# PowerMeter_PowerSupply.net
KiCad netlist of a schematic drawn in Altium Designer
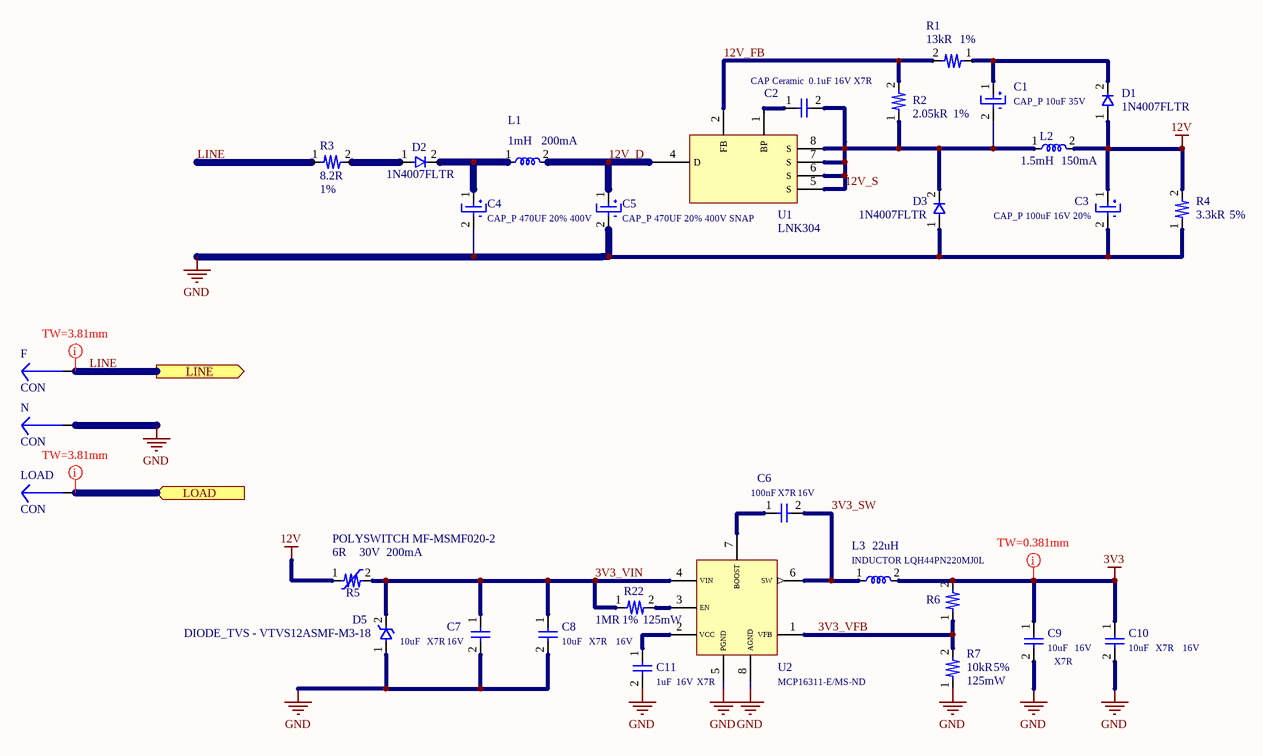
[diagram p0: PowerMeter_PowerSupply.SchDoc]

(export (version "E")
  (design (tool "Eeschema 10.0.6"))
  (components
    (comp (ref "C1")
      (value "CAP_P 10uF 35V")
      (footprint "CAP100RP")
      (description "Cap Aluminum 10uF 35V 20% Radial 2000 hr 85°C Ammo Pack")
      (fields
        (field (name "MANUFACTURER") "Panasonic")
        (field (name "MANUFACTURER PART NUMBER") "ECA-1VM100B")
      )
      (libsource (lib "PowerMeter") (part "CAP_P"))
    )
    (comp (ref "C2")
      (value "CAP Ceramic  0.1uF 16V X7R")
      (footprint "C_0805")
      (description "Cap Ceramic 0.1uF 16V X7R 10% SMD 0805 125C Paper T/R")
      (fields
        (field (name "MANUFACTURER") "Yageo")
        (field (name "MANUFACTURER PART NUMBER") "CC0805KPX7R7BB104")
      )
      (libsource (lib "PowerMeter") (part "CAP_NP"))
    )
    (comp (ref "C3")
      (value "CAP_P 100uF 16V 20%")
      (footprint "CAP100RP")
      (description "Cap Aluminum 100uF 16V 20% (5 X 11mm) Radial 2.5mm 180mA 2000h 85°C Ammo Pack")
      (fields
        (field (name "MANUFACTURER") "Panasonic")
        (field (name "MANUFACTURER PART NUMBER") "ECA-1CM101I")
      )
      (libsource (lib "PowerMeter") (part "CAP_P"))
    )
    (comp (ref "C4")
      (value "CAP_P 470UF 20% 400V")
      (footprint "CAP400RP")
      (description "CAP ALUM 470UF 20% 400V SNAP")
      (fields
        (field (name "MANUFACTURER") "Rubycon")
        (field (name "MANUFACTURER PART NUMBER") "400USG470MEFC25X50")
      )
      (libsource (lib "PowerMeter") (part "CAP_P"))
    )
    (comp (ref "C5")
      (value "CAP_P 470UF 20% 400V SNAP")
      (footprint "CAP400RP")
      (description "CAP ALUM 470UF 20% 400V")
      (fields
        (field (name "MANUFACTURER") "Rubycon")
        (field (name "MANUFACTURER PART NUMBER") "400USG470MEFC25X50")
      )
      (libsource (lib "PowerMeter") (part "CAP_P"))
    )
    (comp (ref "C6")
      (value "CAP Ceramic  0.1uF 16V X7R")
      (footprint "C_0805")
      (description "Cap Ceramic 0.1uF 16V X7R 10% SMD 0805 125C Paper T/R")
      (fields
        (field (name "MANUFACTURER") "Yageo")
        (field (name "MANUFACTURER PART NUMBER") "CC0805KPX7R7BB104")
        (field (name "CAPACITANCE") "100nF")
        (field (name "VOLTAGE RATING (DC)") "16V")
        (field (name "DIELECTRIC") "X7R")
      )
      (libsource (lib "PowerMeter") (part "CAP_NP"))
    )
    (comp (ref "C7")
      (value "CAP Ceramic  10uF 16V X7R")
      (footprint "C_1206")
      (description "CL31 Series 1206 10 uF 16 V ±10% Tolerance X7R Multilayer Ceramic Capacitor")
      (fields
        (field (name "MANUFACTURER") "Samsung")
        (field (name "MANUFACTURER PART NUMBER") "CL31B106KOHNNNF")
        (field (name "CAPACITANCE") "10uF")
        (field (name "DIELECTRIC") "X7R")
        (field (name "VOLTAGE RATING") "16V")
      )
      (libsource (lib "PowerMeter") (part "CAP_NP"))
    )
    (comp (ref "C8")
      (value "CAP Ceramic  10uF 16V X7R")
      (footprint "C_1206")
      (description "CL31 Series 1206 10 uF 16 V ±10% Tolerance X7R Multilayer Ceramic Capacitor")
      (fields
        (field (name "MANUFACTURER") "Samsung")
        (field (name "MANUFACTURER PART NUMBER") "CL31B106KOHNNNF")
        (field (name "CAPACITANCE") "10uF")
        (field (name "DIELECTRIC") "X7R")
        (field (name "VOLTAGE RATING") "16V")
      )
      (libsource (lib "PowerMeter") (part "CAP_NP"))
    )
    (comp (ref "C9")
      (value "CAP Ceramic 10uF 16V X7R")
      (footprint "C_1206")
      (description "CL31 Series 1206 10 uF 16 V ±10% Tolerance X7R Multilayer Ceramic Capacitor")
      (fields
        (field (name "MANUFACTURER") "Samsung")
        (field (name "MANUFACTURER PART NUMBER") "CL31B106KOHNNNF")
        (field (name "CAPACITANCE") "10uF")
        (field (name "DIELECTRIC") "X7R")
        (field (name "VOLTAGE RATING") "16V")
      )
      (libsource (lib "PowerMeter") (part "CAP_NP"))
    )
    (comp (ref "C10")
      (value "CAP Ceramic 10uF 16V X7R")
      (footprint "C_1206")
      (description "CL31 Series 1206 10 uF 16 V ±10% Tolerance X7R Multilayer Ceramic Capacitor")
      (fields
        (field (name "MANUFACTURER") "Samsung")
        (field (name "MANUFACTURER PART NUMBER") "CL31B106KOHNNNF")
        (field (name "CAPACITANCE") "10uF")
        (field (name "DIELECTRIC") "X7R")
        (field (name "VOLTAGE RATING") "16V")
      )
      (libsource (lib "PowerMeter") (part "CAP_NP"))
    )
    (comp (ref "C11")
      (value "CAP Ceramic  1uF 16V X7R")
      (footprint "C_0805")
      (description "Cap Ceramic 1uF 16V X7R 10% Pad SMD 0805 125C T/R")
      (fields
        (field (name "MANUFACTURER") "Samsung")
        (field (name "MANUFACTURER PART NUMBER") "CL21B105KOFNNNF")
        (field (name "CAPACITANCE") "1uF")
        (field (name "DIELECTRIC") "X7R")
        (field (name "VOLTAGE RATING") "16V")
      )
      (libsource (lib "PowerMeter") (part "CAP_NP"))
    )
    (comp (ref "D1")
      (value "DIODE")
      (footprint "SOD_123")
      (description "Standard Rectifier 1000V SOD-123")
      (fields
        (field (name "MANUFACTURER") "Sangdest Microelectronics")
        (field (name "MANUFACTURER PART NUMBER") "1N4007FLTR")
      )
      (libsource (lib "PowerMeter") (part "DIODE"))
    )
    (comp (ref "D2")
      (value "Standard Rectifier 1000V SOD-123")
      (footprint "SOD_123")
      (fields
        (field (name "MANUFACTURER") "Sangdest Microelectronics")
        (field (name "MANUFACTURER PART NUMBER") "1N4007FLTR")
      )
      (libsource (lib "PowerMeter") (part "DIODE"))
    )
    (comp (ref "D3")
      (value "DIODE 1N4007FLTR")
      (footprint "SOD_123")
      (description "Standard Rectifier 1000V SOD-123")
      (fields
        (field (name "MANUFACTURER") "Sangdest Microelectronics")
        (field (name "MANUFACTURER PART NUMBER") "1N4007FLTR")
      )
      (libsource (lib "PowerMeter") (part "DIODE"))
    )
    (comp (ref "D5")
      (value "DIODE_TVS - VTVS12ASMF-M3-18")
      (footprint "SOD_923")
      (description "Esd Protection Diode Smf Do219Ab5%; 12.4V; ir0.05 A; ip19.5A; p400W; cd807Pf")
      (fields
        (field (name "MANUFACTURER") "Vishay")
        (field (name "MANUFACTURER PART NUMBER") "VTVS12ASMF-M3-18")
      )
      (libsource (lib "PowerMeter") (part "DIODE_TVS"))
    )
    (comp (ref "F")
      (value "CON")
      (footprint "HOLE 2.8")
      (description "Hole")
      (libsource (lib "PowerMeter") (part "CON"))
    )
    (comp (ref "L1")
      (value "INDUCTOR RLH0912-102KL")
      (footprint "LQH44")
      (description "Magnetics - Fixed Inductor Through Hole / Bulk, Bag Packaging Rohs Compliant: Yes")
      (fields
        (field (name "MANUFACTURER") "Bourns")
        (field (name "MANUFACTURER PART NUMBER") "RLH0912-102KL")
        (field (name "CURRENT RATING") "200mA")
        (field (name "INDUCTANCE") "1mH")
      )
      (libsource (lib "PowerMeter") (part "INDUCTOR"))
    )
    (comp (ref "L2")
      (value "INDUCTOR AIUR-16-152K")
      (footprint "LQH44")
      (description "Inductor Power Unshielded Drum Core 1500uH 10% 10KHz Ferrite 0.15A 3.5Ohm DCR RDL Box")
      (fields
        (field (name "MANUFACTURER") "Abracon")
        (field (name "MANUFACTURER PART NUMBER") "AIUR-16-152K")
        (field (name "INDUCTANCE") "1.5mH")
        (field (name "CURRENT RATING") "150mA")
      )
      (libsource (lib "PowerMeter") (part "INDUCTOR"))
    )
    (comp (ref "L3")
      (value "INDUCTOR LQH44PN220MJ0L")
      (footprint "LQH44")
      (description "Inductor Power Chip Shielded Wirewound 22uH 20% 100KHz Ferrite 0.55A 0.576Ohm DCR 1515 T/R")
      (fields
        (field (name "MANUFACTURER") "Murata")
        (field (name "MANUFACTURER PART NUMBER") "LQH44PN220MJ0L")
        (field (name "INDUCTANCE") "22uH")
      )
      (libsource (lib "PowerMeter") (part "INDUCTOR"))
    )
    (comp (ref "LOAD")
      (value "CON")
      (footprint "HOLE 2.8")
      (description "Hole")
      (libsource (lib "PowerMeter") (part "CON"))
    )
    (comp (ref "N")
      (value "CON")
      (footprint "HOLE 2.8")
      (description "Hole")
      (libsource (lib "PowerMeter") (part "CON"))
    )
    (comp (ref "R1")
      (value "RES 13K Ohm 1% 1/8W")
      (footprint "R_0805")
      (description "Res Thick Film 0805 13K Ohm 1% 1/8W ±100ppm/°C Molded SMD SMD Paper T/R")
      (fields
        (field (name "MANUFACTURER") "Stackpole Electronics")
        (field (name "MANUFACTURER PART NUMBER") "RMCF0805FG13K0")
        (field (name "RESISTANCE") "13kR")
        (field (name "TOLERANCE") "1%")
      )
      (libsource (lib "PowerMeter") (part "RES"))
    )
    (comp (ref "R2")
      (value "RES 2.05K Ohm 1% 1/8W")
      (footprint "R_0805")
      (description "Res Thick Film 0805 2.05K Ohm 1% 1/8W ±200ppm/°C Molded SMD SMD Paper T/R")
      (fields
        (field (name "MANUFACTURER") "Stackpole Electronics")
        (field (name "MANUFACTURER PART NUMBER") "RMCF0805FG2K05")
        (field (name "RESISTANCE") "2.05kR")
        (field (name "TOLERANCE") "1%")
      )
      (libsource (lib "PowerMeter") (part "RES"))
    )
    (comp (ref "R3")
      (value "RES 0805 8.2 Ohm 1W")
      (footprint "R_0805")
      (description "Res Thin Film 0805 8.2 Ohm 1% 1W ±100ppm/C Pad SMD T/R")
      (fields
        (field (name "MANUFACTURER") "Vishay Dale Thin Film")
        (field (name "MANUFACTURER PART NUMBER") "PCAN0805K8R20FST5")
        (field (name "RESISTANCE") "8.2R")
        (field (name "TOLERANCE") "1%")
      )
      (libsource (lib "PowerMeter") (part "RES"))
    )
    (comp (ref "R4")
      (value "RES  3.3 K Ohms 0.125W; +/-5%")
      (footprint "R_0805")
      (description "Resistor, Thick Film Chip; 3.3 K Ohms; Case 0805; 0.125W; +/-5%; SMD; 200ppm/K; 150V")
      (fields
        (field (name "MANUFACTURER") "Vishay Dale")
        (field (name "MANUFACTURER PART NUMBER") "CRCW08053K30JNTA")
        (field (name "TOLERANCE") "5%")
        (field (name "RESISTANCE") "3.3kR")
      )
      (libsource (lib "PowerMeter") (part "RES"))
    )
    (comp (ref "R5")
      (value "POLYSWITCH MF-MSMF020-2")
      (footprint "NANOSMDC")
      (fields
        (field (name "MANUFACTURER") "Bourns")
        (field (name "MANUFACTURER PART NUMBER") "MF-MSMF020-2")
        (field (name "RESISTANCE") "6R")
        (field (name "HOLD CURRENT") "200mA")
        (field (name "TOLERANCE") "5%")
        (field (name "VOLTAGE RATING (DC)") "30V")
      )
      (libsource (lib "PowerMeter") (part "POLYSWITCH"))
    )
    (comp (ref "R6")
      (value "RES 31.2K Ohm 1% 1/8W")
      (footprint "R_0805")
      (description "Res 31.2K Ohm 1% 1/8W 0805")
      (fields
        (field (name "MANUFACTURER") "KOA Speer")
        (field (name "MANUFACTURER PART NUMBER") "RN73R2ATTD3122F100")
      )
      (libsource (lib "PowerMeter") (part "RES"))
    )
    (comp (ref "R7")
      (value "RES 10K Ohm 1% 1/8W")
      (footprint "R_0805")
      (description "Res Thick Film 0805 10K Ohm 5% 1/8W ±200ppm/°C Molded SMD SMD Paper T/R")
      (fields
        (field (name "MANUFACTURER") "Vishay Dale")
        (field (name "MANUFACTURER PART NUMBER") "CRCW080510K0JNEB")
        (field (name "RESISTANCE") "10kR")
        (field (name "TOLERANCE") "5%")
        (field (name "POWER RATING") "125mW")
      )
      (libsource (lib "PowerMeter") (part "RES"))
    )
    (comp (ref "R22")
      (value "RES 1M Ohm 1% 1/8W")
      (footprint "R_0805")
      (description "Res Thick Film 0805 1M Ohm 1% 1/8W ±200ppm/°C Molded SMD Paper T/R")
      (fields
        (field (name "MANUFACTURER") "Yageo")
        (field (name "MANUFACTURER PART NUMBER") "RV0805FR-071ML")
        (field (name "RESISTANCE") "1MR")
        (field (name "POWER RATING") "125mW")
        (field (name "TOLERANCE") "1%")
      )
      (libsource (lib "PowerMeter") (part "RES"))
    )
    (comp (ref "U1")
      (value "LNK304")
      (footprint "LNK304")
      (description "AC to DC Switching Converter Buck 70kHz T/R 7-Pin SO-C")
      (fields
        (field (name "MANUFACTURER") "Power Integrations")
        (field (name "MANUFACTURER PART NUMBER") "LNK304DN-TL")
      )
      (libsource (lib "PowerMeter") (part "LNK304"))
    )
    (comp (ref "U2")
      (value "STEP-DOWN REGULATOR MCP16311-E/MS-ND")
      (footprint "MCP16311/2")
      (description "Regulador switching step-down")
      (fields (field (name "SUPPLIER PART NUMBER 1") "MCP16311-E/MS-ND"))
      (libsource (lib "PowerMeter") (part "MCP16311/2"))
    )
  )
  (nets
    (net (code "1") (name "/3V3_SW") (class "Default")
      (node (ref "C6") (pin "2") (pintype "passive"))
      (node (ref "L3") (pin "1") (pintype "passive"))
      (node (ref "U2") (pin "6") (pinfunction "SW_6") (pintype "output"))
    )
    (net (code "2") (name "/3V3_VFB") (class "Default")
      (node (ref "R6") (pin "1") (pintype "passive"))
      (node (ref "R7") (pin "2") (pintype "passive"))
      (node (ref "U2") (pin "1") (pinfunction "VFB_1") (pintype "passive"))
    )
    (net (code "3") (name "/3V3_VIN") (class "Default")
      (node (ref "C7") (pin "1") (pintype "passive"))
      (node (ref "C8") (pin "1") (pintype "passive"))
      (node (ref "D5") (pin "2") (pintype "passive"))
      (node (ref "R22") (pin "1") (pintype "passive"))
      (node (ref "R5") (pin "2") (pintype "passive"))
      (node (ref "U2") (pin "4") (pinfunction "VIN_4") (pintype "passive"))
    )
    (net (code "4") (name "/12V_D") (class "Default")
      (node (ref "C5") (pin "1") (pintype "passive"))
      (node (ref "L1") (pin "2") (pintype "passive"))
      (node (ref "U1") (pin "4") (pinfunction "D_4") (pintype "passive"))
    )
    (net (code "5") (name "/12V_FB") (class "Default")
      (node (ref "R1") (pin "2") (pintype "passive"))
      (node (ref "R2") (pin "2") (pintype "passive"))
      (node (ref "U1") (pin "2") (pinfunction "FB_2") (pintype "passive"))
    )
    (net (code "6") (name "/12V_S") (class "Default")
      (node (ref "C1") (pin "2") (pintype "passive"))
      (node (ref "C2") (pin "2") (pintype "passive"))
      (node (ref "D3") (pin "2") (pintype "passive"))
      (node (ref "L2") (pin "1") (pintype "passive"))
      (node (ref "R2") (pin "1") (pintype "passive"))
      (node (ref "U1") (pin "5") (pinfunction "S_5") (pintype "passive"))
      (node (ref "U1") (pin "6") (pinfunction "S_6") (pintype "passive"))
      (node (ref "U1") (pin "7") (pinfunction "S_7") (pintype "passive"))
      (node (ref "U1") (pin "8") (pinfunction "S_8") (pintype "passive"))
    )
    (net (code "7") (name "/LINE") (class "Default")
      (node (ref "F") (pin "1") (pintype "passive"))
      (node (ref "R3") (pin "1") (pintype "passive"))
    )
    (net (code "8") (name "/LOAD") (class "Default") (node (ref "LOAD") (pin "1") (pintype "passive")))
    (net (code "9") (name "3V3") (class "Default")
      (node (ref "C10") (pin "1") (pintype "passive"))
      (node (ref "C9") (pin "1") (pintype "passive"))
      (node (ref "L3") (pin "2") (pintype "passive"))
      (node (ref "R6") (pin "2") (pintype "passive"))
    )
    (net (code "10") (name "12V") (class "Default")
      (node (ref "C3") (pin "1") (pintype "passive"))
      (node (ref "D1") (pin "1") (pintype "passive"))
      (node (ref "L2") (pin "2") (pintype "passive"))
      (node (ref "R4") (pin "2") (pintype "passive"))
      (node (ref "R5") (pin "1") (pintype "passive"))
    )
    (net (code "11") (name "GND") (class "Default")
      (node (ref "C10") (pin "2") (pintype "passive"))
      (node (ref "C11") (pin "2") (pintype "passive"))
      (node (ref "C3") (pin "2") (pintype "passive"))
      (node (ref "C4") (pin "2") (pintype "passive"))
      (node (ref "C5") (pin "2") (pintype "passive"))
      (node (ref "C7") (pin "2") (pintype "passive"))
      (node (ref "C8") (pin "2") (pintype "passive"))
      (node (ref "C9") (pin "2") (pintype "passive"))
      (node (ref "D3") (pin "1") (pintype "passive"))
      (node (ref "D5") (pin "1") (pintype "passive"))
      (node (ref "N") (pin "1") (pintype "passive"))
      (node (ref "R4") (pin "1") (pintype "passive"))
      (node (ref "R7") (pin "1") (pintype "passive"))
      (node (ref "U2") (pin "5") (pinfunction "PGND_5") (pintype "power_in"))
      (node (ref "U2") (pin "8") (pinfunction "AGND_8") (pintype "power_in"))
    )
    (net (code "12") (name "Net-(C1-Pad1)") (class "Default")
      (node (ref "C1") (pin "1") (pintype "passive"))
      (node (ref "D1") (pin "2") (pintype "passive"))
      (node (ref "R1") (pin "1") (pintype "passive"))
    )
    (net (code "13") (name "Net-(C4-Pad1)") (class "Default")
      (node (ref "C4") (pin "1") (pintype "passive"))
      (node (ref "D2") (pin "2") (pintype "passive"))
      (node (ref "L1") (pin "1") (pintype "passive"))
    )
    (net (code "14") (name "Net-(D2-Pad1)") (class "Default")
      (node (ref "D2") (pin "1") (pintype "passive"))
      (node (ref "R3") (pin "2") (pintype "passive"))
    )
    (net (code "15") (name "Net-(U1-BP)") (class "Default")
      (node (ref "C2") (pin "1") (pintype "passive"))
      (node (ref "U1") (pin "1") (pinfunction "BP_1") (pintype "passive"))
    )
    (net (code "16") (name "Net-(U2-BOOST)") (class "Default")
      (node (ref "C6") (pin "1") (pintype "passive"))
      (node (ref "U2") (pin "7") (pinfunction "BOOST_7") (pintype "passive"))
    )
    (net (code "17") (name "Net-(U2-EN)") (class "Default")
      (node (ref "R22") (pin "2") (pintype "passive"))
      (node (ref "U2") (pin "3") (pinfunction "EN_3") (pintype "passive"))
    )
    (net (code "18") (name "Net-(U2-VCC)") (class "Default")
      (node (ref "C11") (pin "1") (pintype "passive"))
      (node (ref "U2") (pin "2") (pinfunction "VCC_2") (pintype "passive"))
    )
  )
)
